# lp5012.net
KiCad netlist of a schematic drawn in Altium Designer
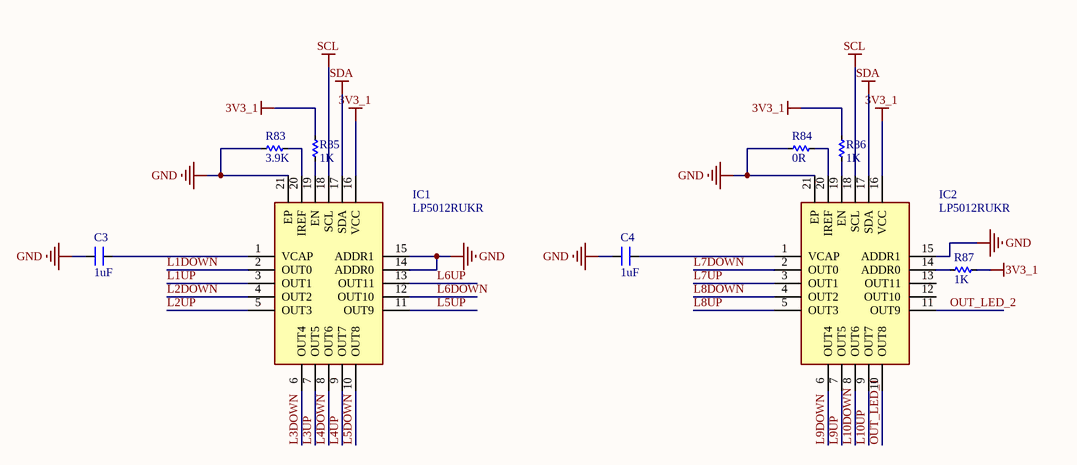
[diagram p0: lp5012.SchDoc]

(export (version "E")
  (design (tool "Eeschema 10.0.6"))
  (components
    (comp (ref "C3") (value "1uF") (footprint "CN-SMD-0603") (libsource (lib "LIBRARY") (part "CN")))
    (comp (ref "C4") (value "1uF") (footprint "CN-SMD-0603") (libsource (lib "LIBRARY") (part "CN")))
    (comp (ref "IC1")
      (value "LP5012RUKR")
      (footprint "SamacSys:QFN40P300X300X80-21N-D")
      (description "Integrated Circuit")
      (fields (field (name "MOUSER PART NUMBER") "595-LP5012RUKR"))
      (libsource (lib "SamacSys") (part "LP5012RUKR"))
    )
    (comp (ref "IC2")
      (value "LP5012RUKR")
      (footprint "SamacSys:QFN40P300X300X80-21N-D")
      (description "Integrated Circuit")
      (fields (field (name "MOUSER PART NUMBER") "595-LP5012RUKR"))
      (libsource (lib "SamacSys") (part "LP5012RUKR"))
    )
    (comp (ref "R83")
      (value "3.9K")
      (footprint "RES-SMD-0603")
      (description "Resistor")
      (fields
        (field (name "MANUFACTURER") "Generic Components")
        (field (name "PUBLISHER") "Altium Hobart Technology Centre")
      )
      (libsource (lib "LIBRARY") (part "Res-SMD"))
    )
    (comp (ref "R84")
      (value "0R")
      (footprint "RES-SMD-0603")
      (description "Resistor")
      (fields
        (field (name "MANUFACTURER") "Generic Components")
        (field (name "PUBLISHER") "Altium Hobart Technology Centre")
      )
      (libsource (lib "LIBRARY") (part "Res-SMD"))
    )
    (comp (ref "R85")
      (value "1K")
      (footprint "RES-SMD-0603")
      (description "Resistor")
      (fields
        (field (name "MANUFACTURER") "Generic Components")
        (field (name "PUBLISHER") "Altium Hobart Technology Centre")
      )
      (libsource (lib "LIBRARY") (part "Res-SMD"))
    )
    (comp (ref "R86")
      (value "1K")
      (footprint "RES-SMD-0603")
      (description "Resistor")
      (fields
        (field (name "MANUFACTURER") "Generic Components")
        (field (name "PUBLISHER") "Altium Hobart Technology Centre")
      )
      (libsource (lib "LIBRARY") (part "Res-SMD"))
    )
    (comp (ref "R87")
      (value "1K")
      (footprint "RES-SMD-0603")
      (description "Resistor")
      (fields
        (field (name "MANUFACTURER") "Generic Components")
        (field (name "PUBLISHER") "Altium Hobart Technology Centre")
      )
      (libsource (lib "LIBRARY") (part "Res-SMD"))
    )
  )
  (nets
    (net (code "1") (name "/L1DOWN") (class "Default")
      (node (ref "IC1") (pin "2") (pinfunction "OUT0_2") (pintype "passive"))
    )
    (net (code "2") (name "/L1UP") (class "Default")
      (node (ref "IC1") (pin "3") (pinfunction "OUT1_3") (pintype "passive"))
    )
    (net (code "3") (name "/L2DOWN") (class "Default")
      (node (ref "IC1") (pin "4") (pinfunction "OUT2_4") (pintype "passive"))
    )
    (net (code "4") (name "/L2UP") (class "Default")
      (node (ref "IC1") (pin "5") (pinfunction "OUT3_5") (pintype "passive"))
    )
    (net (code "5") (name "/L3DOWN") (class "Default")
      (node (ref "IC1") (pin "6") (pinfunction "OUT4_6") (pintype "passive"))
    )
    (net (code "6") (name "/L3UP") (class "Default")
      (node (ref "IC1") (pin "7") (pinfunction "OUT5_7") (pintype "passive"))
    )
    (net (code "7") (name "/L4DOWN") (class "Default")
      (node (ref "IC1") (pin "8") (pinfunction "OUT6_8") (pintype "passive"))
    )
    (net (code "8") (name "/L4UP") (class "Default")
      (node (ref "IC1") (pin "9") (pinfunction "OUT7_9") (pintype "passive"))
    )
    (net (code "9") (name "/L5DOWN") (class "Default")
      (node (ref "IC1") (pin "10") (pinfunction "OUT8_10") (pintype "passive"))
    )
    (net (code "10") (name "/L5UP") (class "Default")
      (node (ref "IC1") (pin "11") (pinfunction "OUT9_11") (pintype "passive"))
    )
    (net (code "11") (name "/L6DOWN") (class "Default")
      (node (ref "IC1") (pin "12") (pinfunction "OUT10_12") (pintype "passive"))
    )
    (net (code "12") (name "/L6UP") (class "Default")
      (node (ref "IC1") (pin "13") (pinfunction "OUT11_13") (pintype "passive"))
    )
    (net (code "13") (name "/L7DOWN") (class "Default")
      (node (ref "IC2") (pin "2") (pinfunction "OUT0_2") (pintype "passive"))
    )
    (net (code "14") (name "/L7UP") (class "Default")
      (node (ref "IC2") (pin "3") (pinfunction "OUT1_3") (pintype "passive"))
    )
    (net (code "15") (name "/L8DOWN") (class "Default")
      (node (ref "IC2") (pin "4") (pinfunction "OUT2_4") (pintype "passive"))
    )
    (net (code "16") (name "/L8UP") (class "Default")
      (node (ref "IC2") (pin "5") (pinfunction "OUT3_5") (pintype "passive"))
    )
    (net (code "17") (name "/L9DOWN") (class "Default")
      (node (ref "IC2") (pin "6") (pinfunction "OUT4_6") (pintype "passive"))
    )
    (net (code "18") (name "/L9UP") (class "Default")
      (node (ref "IC2") (pin "7") (pinfunction "OUT5_7") (pintype "passive"))
    )
    (net (code "19") (name "/L10DOWN") (class "Default")
      (node (ref "IC2") (pin "8") (pinfunction "OUT6_8") (pintype "passive"))
    )
    (net (code "20") (name "/L10UP") (class "Default")
      (node (ref "IC2") (pin "9") (pinfunction "OUT7_9") (pintype "passive"))
    )
    (net (code "21") (name "/OUT_LED_1") (class "Default")
      (node (ref "IC2") (pin "10") (pinfunction "OUT8_10") (pintype "passive"))
    )
    (net (code "22") (name "/OUT_LED_2") (class "Default")
      (node (ref "IC2") (pin "11") (pinfunction "OUT9_11") (pintype "passive"))
    )
    (net (code "23") (name "3V3_1") (class "Default")
      (node (ref "IC1") (pin "16") (pinfunction "VCC_16") (pintype "passive"))
      (node (ref "IC2") (pin "16") (pinfunction "VCC_16") (pintype "passive"))
      (node (ref "R85") (pin "1") (pinfunction "1_1") (pintype "passive"))
      (node (ref "R86") (pin "1") (pinfunction "1_1") (pintype "passive"))
      (node (ref "R87") (pin "2") (pinfunction "2_2") (pintype "passive"))
    )
    (net (code "24") (name "GND") (class "Default")
      (node (ref "C3") (pin "1") (pinfunction "1_1") (pintype "passive"))
      (node (ref "C4") (pin "1") (pinfunction "1_1") (pintype "passive"))
      (node (ref "IC1") (pin "14") (pinfunction "ADDR0_14") (pintype "passive"))
      (node (ref "IC1") (pin "15") (pinfunction "ADDR1_15") (pintype "passive"))
      (node (ref "IC1") (pin "21") (pinfunction "EP_21") (pintype "passive"))
      (node (ref "IC2") (pin "15") (pinfunction "ADDR1_15") (pintype "passive"))
      (node (ref "IC2") (pin "21") (pinfunction "EP_21") (pintype "passive"))
      (node (ref "R83") (pin "2") (pinfunction "2_2") (pintype "passive"))
      (node (ref "R84") (pin "2") (pinfunction "2_2") (pintype "passive"))
    )
    (net (code "25") (name "Net-(IC1-EN)") (class "Default")
      (node (ref "IC1") (pin "19") (pinfunction "EN_19") (pintype "passive"))
      (node (ref "R85") (pin "2") (pinfunction "2_2") (pintype "passive"))
    )
    (net (code "26") (name "Net-(IC1-IREF)") (class "Default")
      (node (ref "IC1") (pin "20") (pinfunction "IREF_20") (pintype "passive"))
      (node (ref "R83") (pin "1") (pinfunction "1_1") (pintype "passive"))
    )
    (net (code "27") (name "Net-(IC1-VCAP)") (class "Default")
      (node (ref "C3") (pin "2") (pinfunction "2_2") (pintype "passive"))
      (node (ref "IC1") (pin "1") (pinfunction "VCAP_1") (pintype "passive"))
    )
    (net (code "28") (name "Net-(IC2-ADDR0)") (class "Default")
      (node (ref "IC2") (pin "14") (pinfunction "ADDR0_14") (pintype "passive"))
      (node (ref "R87") (pin "1") (pinfunction "1_1") (pintype "passive"))
    )
    (net (code "29") (name "Net-(IC2-EN)") (class "Default")
      (node (ref "IC2") (pin "19") (pinfunction "EN_19") (pintype "passive"))
      (node (ref "R86") (pin "2") (pinfunction "2_2") (pintype "passive"))
    )
    (net (code "30") (name "Net-(IC2-IREF)") (class "Default")
      (node (ref "IC2") (pin "20") (pinfunction "IREF_20") (pintype "passive"))
      (node (ref "R84") (pin "1") (pinfunction "1_1") (pintype "passive"))
    )
    (net (code "31") (name "Net-(IC2-VCAP)") (class "Default")
      (node (ref "C4") (pin "2") (pinfunction "2_2") (pintype "passive"))
      (node (ref "IC2") (pin "1") (pinfunction "VCAP_1") (pintype "passive"))
    )
    (net (code "32") (name "SCL") (class "Default")
      (node (ref "IC1") (pin "18") (pinfunction "SCL_18") (pintype "passive"))
      (node (ref "IC2") (pin "18") (pinfunction "SCL_18") (pintype "passive"))
    )
    (net (code "33") (name "SDA") (class "Default")
      (node (ref "IC1") (pin "17") (pinfunction "SDA_17") (pintype "passive"))
      (node (ref "IC2") (pin "17") (pinfunction "SDA_17") (pintype "passive"))
    )
    (net (code "34") (name "unconnected-(IC2-OUT10-Pad12)") (class "Default")
      (node (ref "IC2") (pin "12") (pinfunction "OUT10_12") (pintype "passive"))
    )
    (net (code "35") (name "unconnected-(IC2-OUT11-Pad13)") (class "Default")
      (node (ref "IC2") (pin "13") (pinfunction "OUT11_13") (pintype "passive"))
    )
  )
)
